# rev02_15.net
KiCad netlist of a schematic drawn in Altium Designer
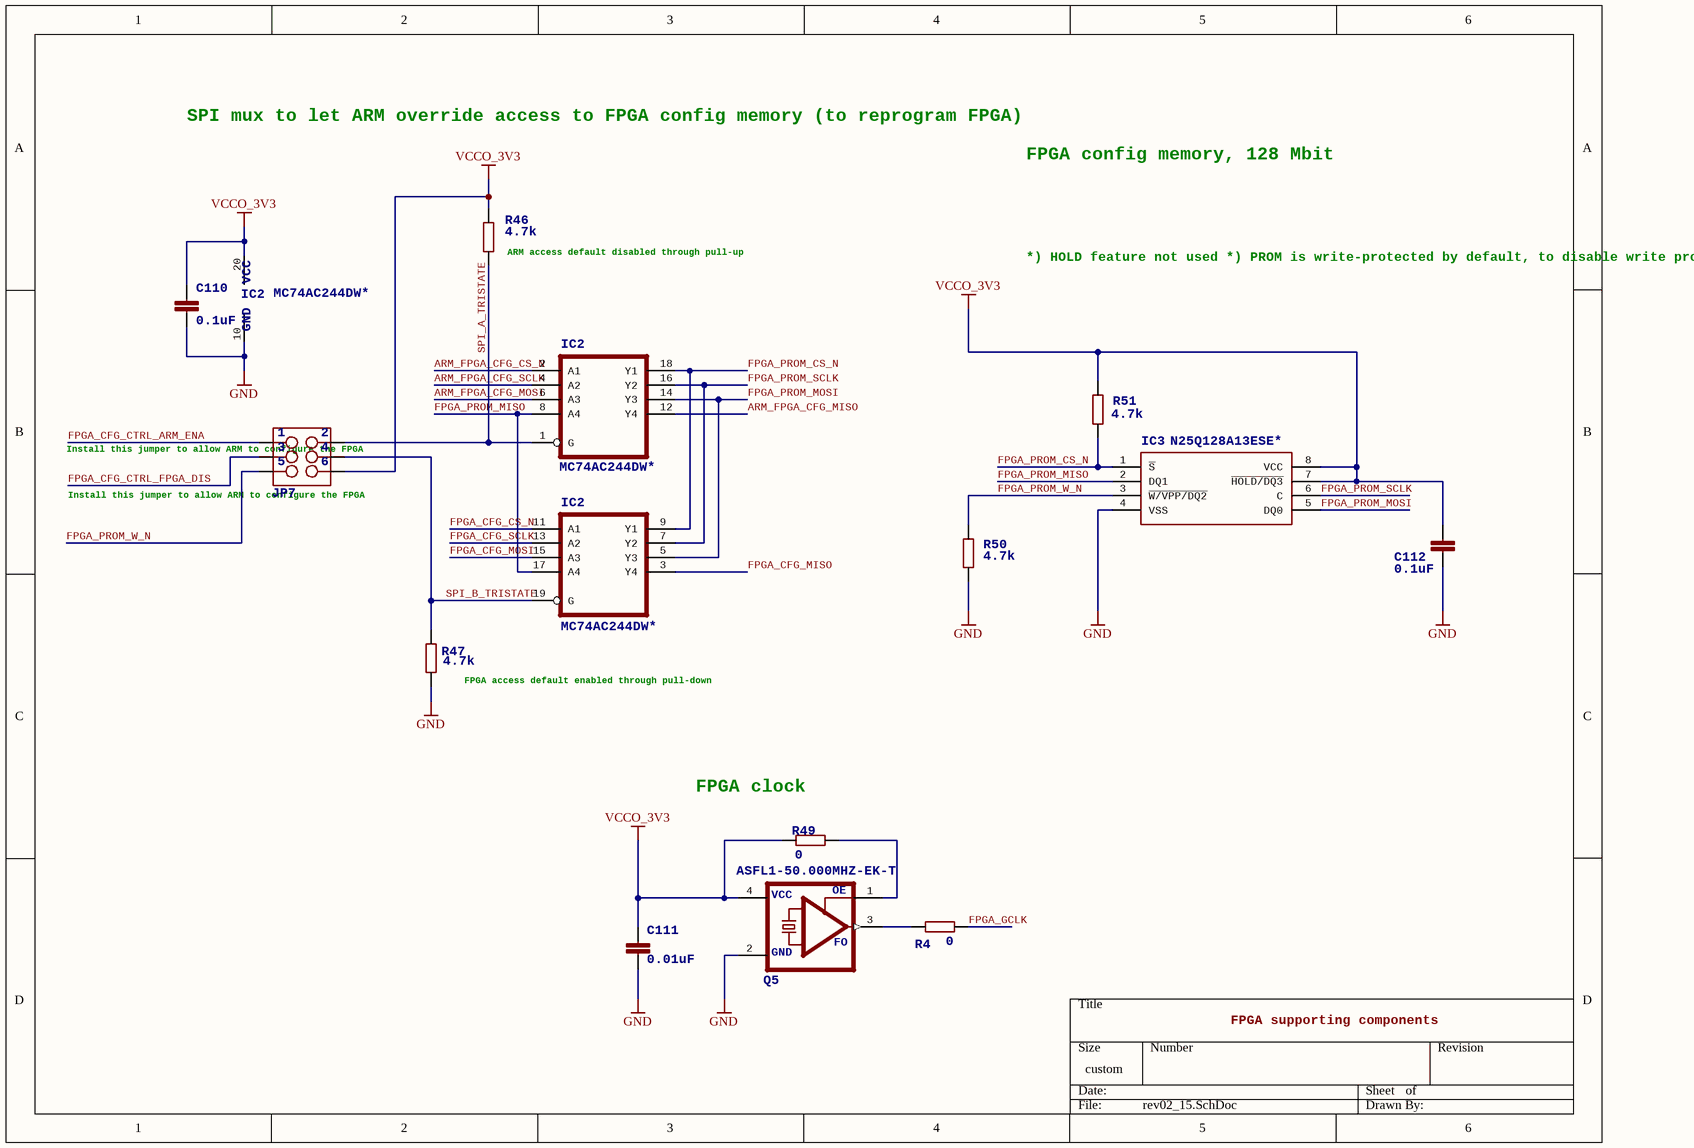
[diagram p0: rev02_15.SchDoc]

(export (version "E")
  (design (tool "Eeschema 10.0.6"))
  (components
    (comp (ref "C110")
      (value "0.1uF")
      (footprint "C_0402")
      (description "0402 CAPACITOR")
      (libsource (lib "resistor") (part "C-EUC0402"))
    )
    (comp (ref "C111")
      (value "0.01uF")
      (footprint "C_0402")
      (description "0402 CAPACITOR")
      (fields (field (name "TOLERANCE") "10%") (field (name ">NAME") "C111"))
      (libsource (lib "resistor") (part "C-EUC0402"))
    )
    (comp (ref "C112")
      (value "0.1uF")
      (footprint "C_0402")
      (description "0402 CAPACITOR")
      (libsource (lib "resistor") (part "C-EUC0402"))
    )
    (comp (ref "IC2")
      (value "MC74AC244DW*")
      (footprint "SO20W")
      (description "Octal BUFFER and LINE DRIVER, 3-state")
      (fields (field (name ">NAME") "IC2") (field (name "GND") "GND") (field (name "VCC") "VCC"))
      (libsource (lib "74xx-eu") (part "74*244DW"))
    )
    (comp (ref "IC3")
      (value "N25Q128A13ESE*")
      (footprint "SO08")
      (description "NOR Flash")
      (fields (field (name ">NAME") "IC3"))
      (libsource (lib "altera-configdevices") (part "N25Q128A13ES"))
    )
    (comp (ref "JP7")
      (value "M03X2NO_SILK")
      (footprint "PLD-6")
      (description "2x3 .1\" header")
      (fields
        (field (name "1") "1")
        (field (name "2") "2")
        (field (name "3") "3")
        (field (name "4") "4")
        (field (name "5") "5")
        (field (name "6") "6")
      )
      (libsource (lib "SparkFun-Connectors") (part "M03X2NO_SILK"))
    )
    (comp (ref "Q5")
      (value "ASFL1-50.000MHZ-EK-T")
      (footprint "ASF")
      (fields
        (field (name "MF") "Abracon Corporation")
        (field (name "MPN") "ASFL1-125.000MHZ-EC-T")
        (field (name "GND") "GND")
        (field (name "VCC") "VCC")
        (field (name "FO") "FO")
        (field (name "OE") "OE")
      )
      (libsource (lib "rev02_1") (part "ASF*"))
    )
    (comp (ref "R4")
      (value "0")
      (footprint "R_0402")
      (description "0402 Resistor 5%")
      (fields (field (name ">NAME") "R4"))
      (libsource (lib "resistor") (part "R-EU_R0402"))
    )
    (comp (ref "R46")
      (value "4.7k")
      (footprint "R_0402")
      (description "0402 Resistor 5%")
      (fields (field (name "TOLERANCE") "5%") (field (name ">NAME") "R46"))
      (libsource (lib "resistor") (part "R-EU_R0402"))
    )
    (comp (ref "R47")
      (value "4.7k")
      (footprint "R_0402")
      (description "0402 Resistor 5%")
      (fields (field (name "TOLERANCE") "5%") (field (name ">NAME") "R47"))
      (libsource (lib "resistor") (part "R-EU_R0402"))
    )
    (comp (ref "R49")
      (value "0")
      (footprint "R_0402")
      (description "0402 Resistor 5%")
      (fields (field (name ">NAME") "R49"))
      (libsource (lib "resistor") (part "R-EU_R0402"))
    )
    (comp (ref "R50")
      (value "4.7k")
      (footprint "R_0402")
      (description "0402 Resistor 5%")
      (fields (field (name "TOLERANCE") "5%") (field (name ">NAME") "R50"))
      (libsource (lib "resistor") (part "R-EU_R0402"))
    )
    (comp (ref "R51")
      (value "4.7k")
      (footprint "R_0402")
      (description "0402 Resistor 5%")
      (fields (field (name "TOLERANCE") "5%") (field (name ">NAME") "R51"))
      (libsource (lib "resistor") (part "R-EU_R0402"))
    )
  )
  (nets
    (net (code "1") (name "/ARM_FPGA_CFG_CS_N") (class "Default")
      (node (ref "IC2") (pin "2") (pinfunction "A1_2") (pintype "passive"))
    )
    (net (code "2") (name "/ARM_FPGA_CFG_MISO") (class "Default")
      (node (ref "IC2") (pin "12") (pinfunction "Y4_12") (pintype "tri_state"))
    )
    (net (code "3") (name "/ARM_FPGA_CFG_MOSI") (class "Default")
      (node (ref "IC2") (pin "6") (pinfunction "A3_6") (pintype "passive"))
    )
    (net (code "4") (name "/ARM_FPGA_CFG_SCLK") (class "Default")
      (node (ref "IC2") (pin "4") (pinfunction "A2_4") (pintype "passive"))
    )
    (net (code "5") (name "/FPGA_CFG_CS_N") (class "Default")
      (node (ref "IC2") (pin "11") (pinfunction "A1_11") (pintype "passive"))
    )
    (net (code "6") (name "/FPGA_CFG_CTRL_ARM_ENA") (class "Default")
      (node (ref "JP7") (pin "1") (pinfunction "1_1") (pintype "passive"))
    )
    (net (code "7") (name "/FPGA_CFG_CTRL_FPGA_DIS") (class "Default")
      (node (ref "JP7") (pin "3") (pinfunction "3_3") (pintype "passive"))
    )
    (net (code "8") (name "/FPGA_CFG_MISO") (class "Default")
      (node (ref "IC2") (pin "3") (pinfunction "Y4_3") (pintype "tri_state"))
    )
    (net (code "9") (name "/FPGA_CFG_MOSI") (class "Default")
      (node (ref "IC2") (pin "15") (pinfunction "A3_15") (pintype "passive"))
    )
    (net (code "10") (name "/FPGA_CFG_SCLK") (class "Default")
      (node (ref "IC2") (pin "13") (pinfunction "A2_13") (pintype "passive"))
    )
    (net (code "11") (name "/FPGA_GCLK") (class "Default")
      (node (ref "R4") (pin "1") (pinfunction "1_1") (pintype "passive"))
    )
    (net (code "12") (name "/FPGA_PROM_CS_N") (class "Default")
      (node (ref "IC2") (pin "18") (pinfunction "Y1_18") (pintype "tri_state"))
      (node (ref "IC2") (pin "9") (pinfunction "Y1_9") (pintype "tri_state"))
      (node (ref "IC3") (pin "1") (pinfunction "~{S}_1") (pintype "passive"))
      (node (ref "R51") (pin "1") (pinfunction "1_1") (pintype "passive"))
    )
    (net (code "13") (name "/FPGA_PROM_MISO") (class "Default")
      (node (ref "IC2") (pin "17") (pinfunction "A4_17") (pintype "passive"))
      (node (ref "IC2") (pin "8") (pinfunction "A4_8") (pintype "passive"))
      (node (ref "IC3") (pin "2") (pinfunction "DQ1_2") (pintype "passive"))
    )
    (net (code "14") (name "/FPGA_PROM_MOSI") (class "Default")
      (node (ref "IC2") (pin "14") (pinfunction "Y3_14") (pintype "tri_state"))
      (node (ref "IC2") (pin "5") (pinfunction "Y3_5") (pintype "tri_state"))
      (node (ref "IC3") (pin "5") (pinfunction "DQ0_5") (pintype "passive"))
    )
    (net (code "15") (name "/FPGA_PROM_SCLK") (class "Default")
      (node (ref "IC2") (pin "16") (pinfunction "Y2_16") (pintype "tri_state"))
      (node (ref "IC2") (pin "7") (pinfunction "Y2_7") (pintype "tri_state"))
      (node (ref "IC3") (pin "6") (pinfunction "C_6") (pintype "passive"))
    )
    (net (code "16") (name "/FPGA_PROM_W_N") (class "Default")
      (node (ref "IC3") (pin "3") (pinfunction "~{W/VPP/DQ2}_3") (pintype "passive"))
      (node (ref "JP7") (pin "5") (pinfunction "5_5") (pintype "passive"))
      (node (ref "R50") (pin "2") (pinfunction "2_2") (pintype "passive"))
    )
    (net (code "17") (name "/SPI_A_TRISTATE") (class "Default")
      (node (ref "IC2") (pin "1") (pinfunction "G_1") (pintype "passive"))
      (node (ref "JP7") (pin "2") (pinfunction "2_2") (pintype "passive"))
      (node (ref "R46") (pin "1") (pinfunction "1_1") (pintype "passive"))
    )
    (net (code "18") (name "/SPI_B_TRISTATE") (class "Default")
      (node (ref "IC2") (pin "19") (pinfunction "G_19") (pintype "passive"))
      (node (ref "JP7") (pin "4") (pinfunction "4_4") (pintype "passive"))
      (node (ref "R47") (pin "1") (pinfunction "1_1") (pintype "passive"))
    )
    (net (code "19") (name "GND") (class "Default")
      (node (ref "C110") (pin "2") (pinfunction "2_2") (pintype "passive"))
      (node (ref "C111") (pin "2") (pinfunction "2_2") (pintype "passive"))
      (node (ref "C112") (pin "2") (pinfunction "2_2") (pintype "passive"))
      (node (ref "IC2") (pin "10") (pinfunction "GND_10") (pintype "power_in"))
      (node (ref "IC3") (pin "4") (pinfunction "VSS_4") (pintype "passive"))
      (node (ref "Q5") (pin "2") (pinfunction "GND_2") (pintype "power_in"))
      (node (ref "R47") (pin "2") (pinfunction "2_2") (pintype "passive"))
      (node (ref "R50") (pin "1") (pinfunction "1_1") (pintype "passive"))
    )
    (net (code "20") (name "Net-(Q5-FO)") (class "Default")
      (node (ref "Q5") (pin "3") (pinfunction "FO_3") (pintype "output"))
      (node (ref "R4") (pin "2") (pinfunction "2_2") (pintype "passive"))
    )
    (net (code "21") (name "Net-(Q5-OE)") (class "Default")
      (node (ref "Q5") (pin "1") (pinfunction "OE_1") (pintype "passive"))
      (node (ref "R49") (pin "1") (pinfunction "1_1") (pintype "passive"))
    )
    (net (code "22") (name "VCCO_3V3") (class "Default")
      (node (ref "C110") (pin "1") (pinfunction "1_1") (pintype "passive"))
      (node (ref "C111") (pin "1") (pinfunction "1_1") (pintype "passive"))
      (node (ref "C112") (pin "1") (pinfunction "1_1") (pintype "passive"))
      (node (ref "IC2") (pin "20") (pinfunction "VCC_20") (pintype "power_in"))
      (node (ref "IC3") (pin "7") (pinfunction "~{HOLD/DQ3}_7") (pintype "passive"))
      (node (ref "IC3") (pin "8") (pinfunction "VCC_8") (pintype "passive"))
      (node (ref "JP7") (pin "6") (pinfunction "6_6") (pintype "passive"))
      (node (ref "Q5") (pin "4") (pinfunction "VCC_4") (pintype "power_in"))
      (node (ref "R46") (pin "2") (pinfunction "2_2") (pintype "passive"))
      (node (ref "R49") (pin "2") (pinfunction "2_2") (pintype "passive"))
      (node (ref "R51") (pin "2") (pinfunction "2_2") (pintype "passive"))
    )
  )
)
